# PhaseShifterA.net
KiCad netlist of a schematic drawn in Altium Designer
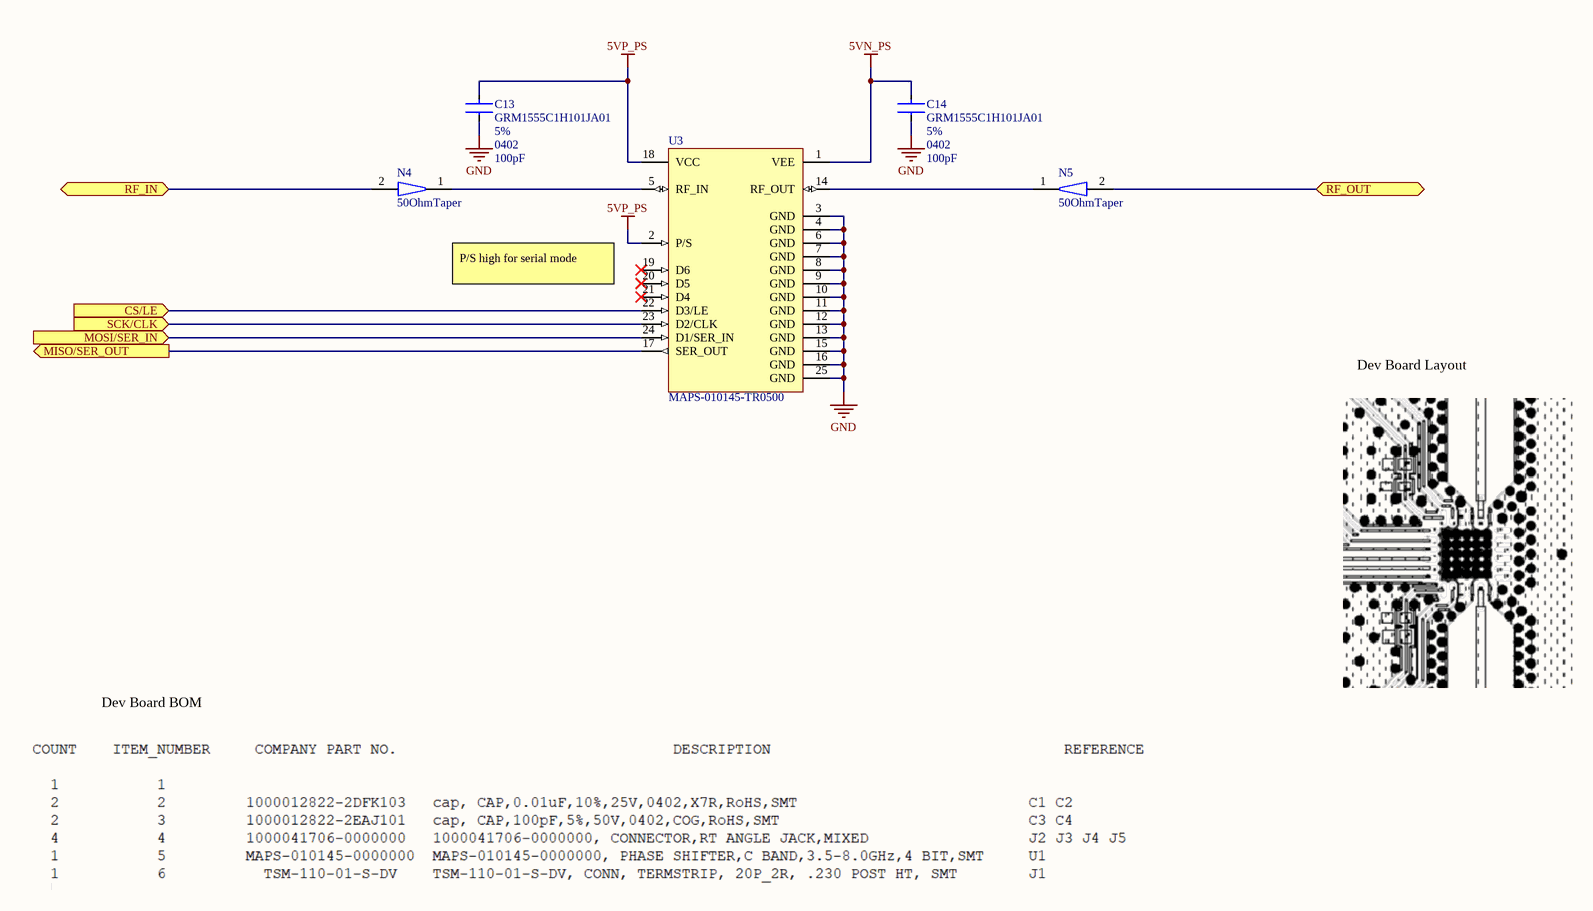
[diagram p0: PhaseShifterA.SchDoc]

(export (version "E")
  (design (tool "Eeschema 10.0.6"))
  (components
    (comp (ref "C13")
      (value "GRM1555C1H101JA01")
      (footprint "Capacitor0402_Murata")
      (description "100 pF ±5% 50V Ceramic Capacitor C0G, NP0 0402 (1005 Metric)")
      (fields
        (field (name "TOLERANCE") "5%")
        (field (name "PACKAGE") "0402")
        (field (name "ALTIUM_VALUE") "100pF")
      )
      (libsource (lib "EECS430PhasedArray") (part "GRM1555C1H101JA01"))
    )
    (comp (ref "C14")
      (value "GRM1555C1H101JA01")
      (footprint "Capacitor0402_Murata")
      (description "100 pF ±5% 50V Ceramic Capacitor C0G, NP0 0402 (1005 Metric)")
      (fields
        (field (name "TOLERANCE") "5%")
        (field (name "PACKAGE") "0402")
        (field (name "ALTIUM_VALUE") "100pF")
      )
      (libsource (lib "EECS430PhasedArray") (part "GRM1555C1H101JA01"))
    )
    (comp (ref "N4")
      (value "50OhmTaper")
      (footprint "50OhmTaper")
      (description "Triangular taper from 50 Ohms to 0402 width")
      (libsource (lib "EECS430PhasedArray") (part "50OhmTaper"))
    )
    (comp (ref "N5")
      (value "50OhmTaper")
      (footprint "50OhmTaper")
      (description "Triangular taper from 50 Ohms to 0402 width")
      (libsource (lib "EECS430PhasedArray") (part "50OhmTaper"))
    )
    (comp (ref "U3")
      (value "MAPS-010145-TR0500")
      (footprint "MAPS-010145-TR0500_QFN50P400X400X100_HS-25N")
      (description "Phase Detectors / Shifters 3.5-6.0GHz 4-Bit Step 22.5 deg.")
      (libsource (lib "EECS430PhasedArray") (part "MAPS-010145-TR0500"))
    )
  )
  (nets
    (net (code "1") (name "/CS{slash}LE") (class "Default")
      (node (ref "U3") (pin "22") (pinfunction "D3/LE_22") (pintype "input"))
    )
    (net (code "2") (name "/MISO{slash}SER_OUT") (class "Default")
      (node (ref "U3") (pin "17") (pinfunction "SER_OUT_17") (pintype "output"))
    )
    (net (code "3") (name "/MOSI{slash}SER_IN") (class "Default")
      (node (ref "U3") (pin "24") (pinfunction "D1/SER_IN_24") (pintype "input"))
    )
    (net (code "4") (name "/RF_IN") (class "Default")
      (node (ref "N4") (pin "2") (pinfunction "2_2") (pintype "passive"))
    )
    (net (code "5") (name "/RF_OUT") (class "Default")
      (node (ref "N5") (pin "2") (pinfunction "2_2") (pintype "passive"))
    )
    (net (code "6") (name "/SCK{slash}CLK") (class "Default")
      (node (ref "U3") (pin "23") (pinfunction "D2/CLK_23") (pintype "input"))
    )
    (net (code "7") (name "5VN_PS") (class "Default")
      (node (ref "C14") (pin "1") (pinfunction "1_1") (pintype "passive"))
      (node (ref "U3") (pin "1") (pinfunction "VEE_1") (pintype "power_in"))
    )
    (net (code "8") (name "5VP_PS") (class "Default")
      (node (ref "C13") (pin "1") (pinfunction "1_1") (pintype "passive"))
      (node (ref "U3") (pin "18") (pinfunction "VCC_18") (pintype "power_in"))
      (node (ref "U3") (pin "2") (pinfunction "P/S_2") (pintype "input"))
    )
    (net (code "9") (name "GND") (class "Default")
      (node (ref "C13") (pin "2") (pinfunction "2_2") (pintype "passive"))
      (node (ref "C14") (pin "2") (pinfunction "2_2") (pintype "passive"))
      (node (ref "U3") (pin "10") (pinfunction "GND_10") (pintype "power_in"))
      (node (ref "U3") (pin "11") (pinfunction "GND_11") (pintype "power_in"))
      (node (ref "U3") (pin "12") (pinfunction "GND_12") (pintype "power_in"))
      (node (ref "U3") (pin "13") (pinfunction "GND_13") (pintype "power_in"))
      (node (ref "U3") (pin "15") (pinfunction "GND_15") (pintype "power_in"))
      (node (ref "U3") (pin "16") (pinfunction "GND_16") (pintype "power_in"))
      (node (ref "U3") (pin "25") (pinfunction "GND_25") (pintype "power_in"))
      (node (ref "U3") (pin "3") (pinfunction "GND_3") (pintype "power_in"))
      (node (ref "U3") (pin "4") (pinfunction "GND_4") (pintype "power_in"))
      (node (ref "U3") (pin "6") (pinfunction "GND_6") (pintype "power_in"))
      (node (ref "U3") (pin "7") (pinfunction "GND_7") (pintype "power_in"))
      (node (ref "U3") (pin "8") (pinfunction "GND_8") (pintype "power_in"))
      (node (ref "U3") (pin "9") (pinfunction "GND_9") (pintype "power_in"))
    )
    (net (code "10") (name "Net-(U3-RF_IN)") (class "Default")
      (node (ref "N4") (pin "1") (pinfunction "1_1") (pintype "passive"))
      (node (ref "U3") (pin "5") (pinfunction "RF_IN_5") (pintype "bidirectional"))
    )
    (net (code "11") (name "Net-(U3-RF_OUT)") (class "Default")
      (node (ref "N5") (pin "1") (pinfunction "1_1") (pintype "passive"))
      (node (ref "U3") (pin "14") (pinfunction "RF_OUT_14") (pintype "bidirectional"))
    )
    (net (code "12") (name "unconnected-(U3-D4-Pad21)") (class "Default")
      (node (ref "U3") (pin "21") (pinfunction "D4_21") (pintype "input+no_connect"))
    )
    (net (code "13") (name "unconnected-(U3-D5-Pad20)") (class "Default")
      (node (ref "U3") (pin "20") (pinfunction "D5_20") (pintype "input+no_connect"))
    )
    (net (code "14") (name "unconnected-(U3-D6-Pad19)") (class "Default")
      (node (ref "U3") (pin "19") (pinfunction "D6_19") (pintype "input+no_connect"))
    )
  )
)
